# io.net
KiCad netlist of a schematic drawn in EAGLE
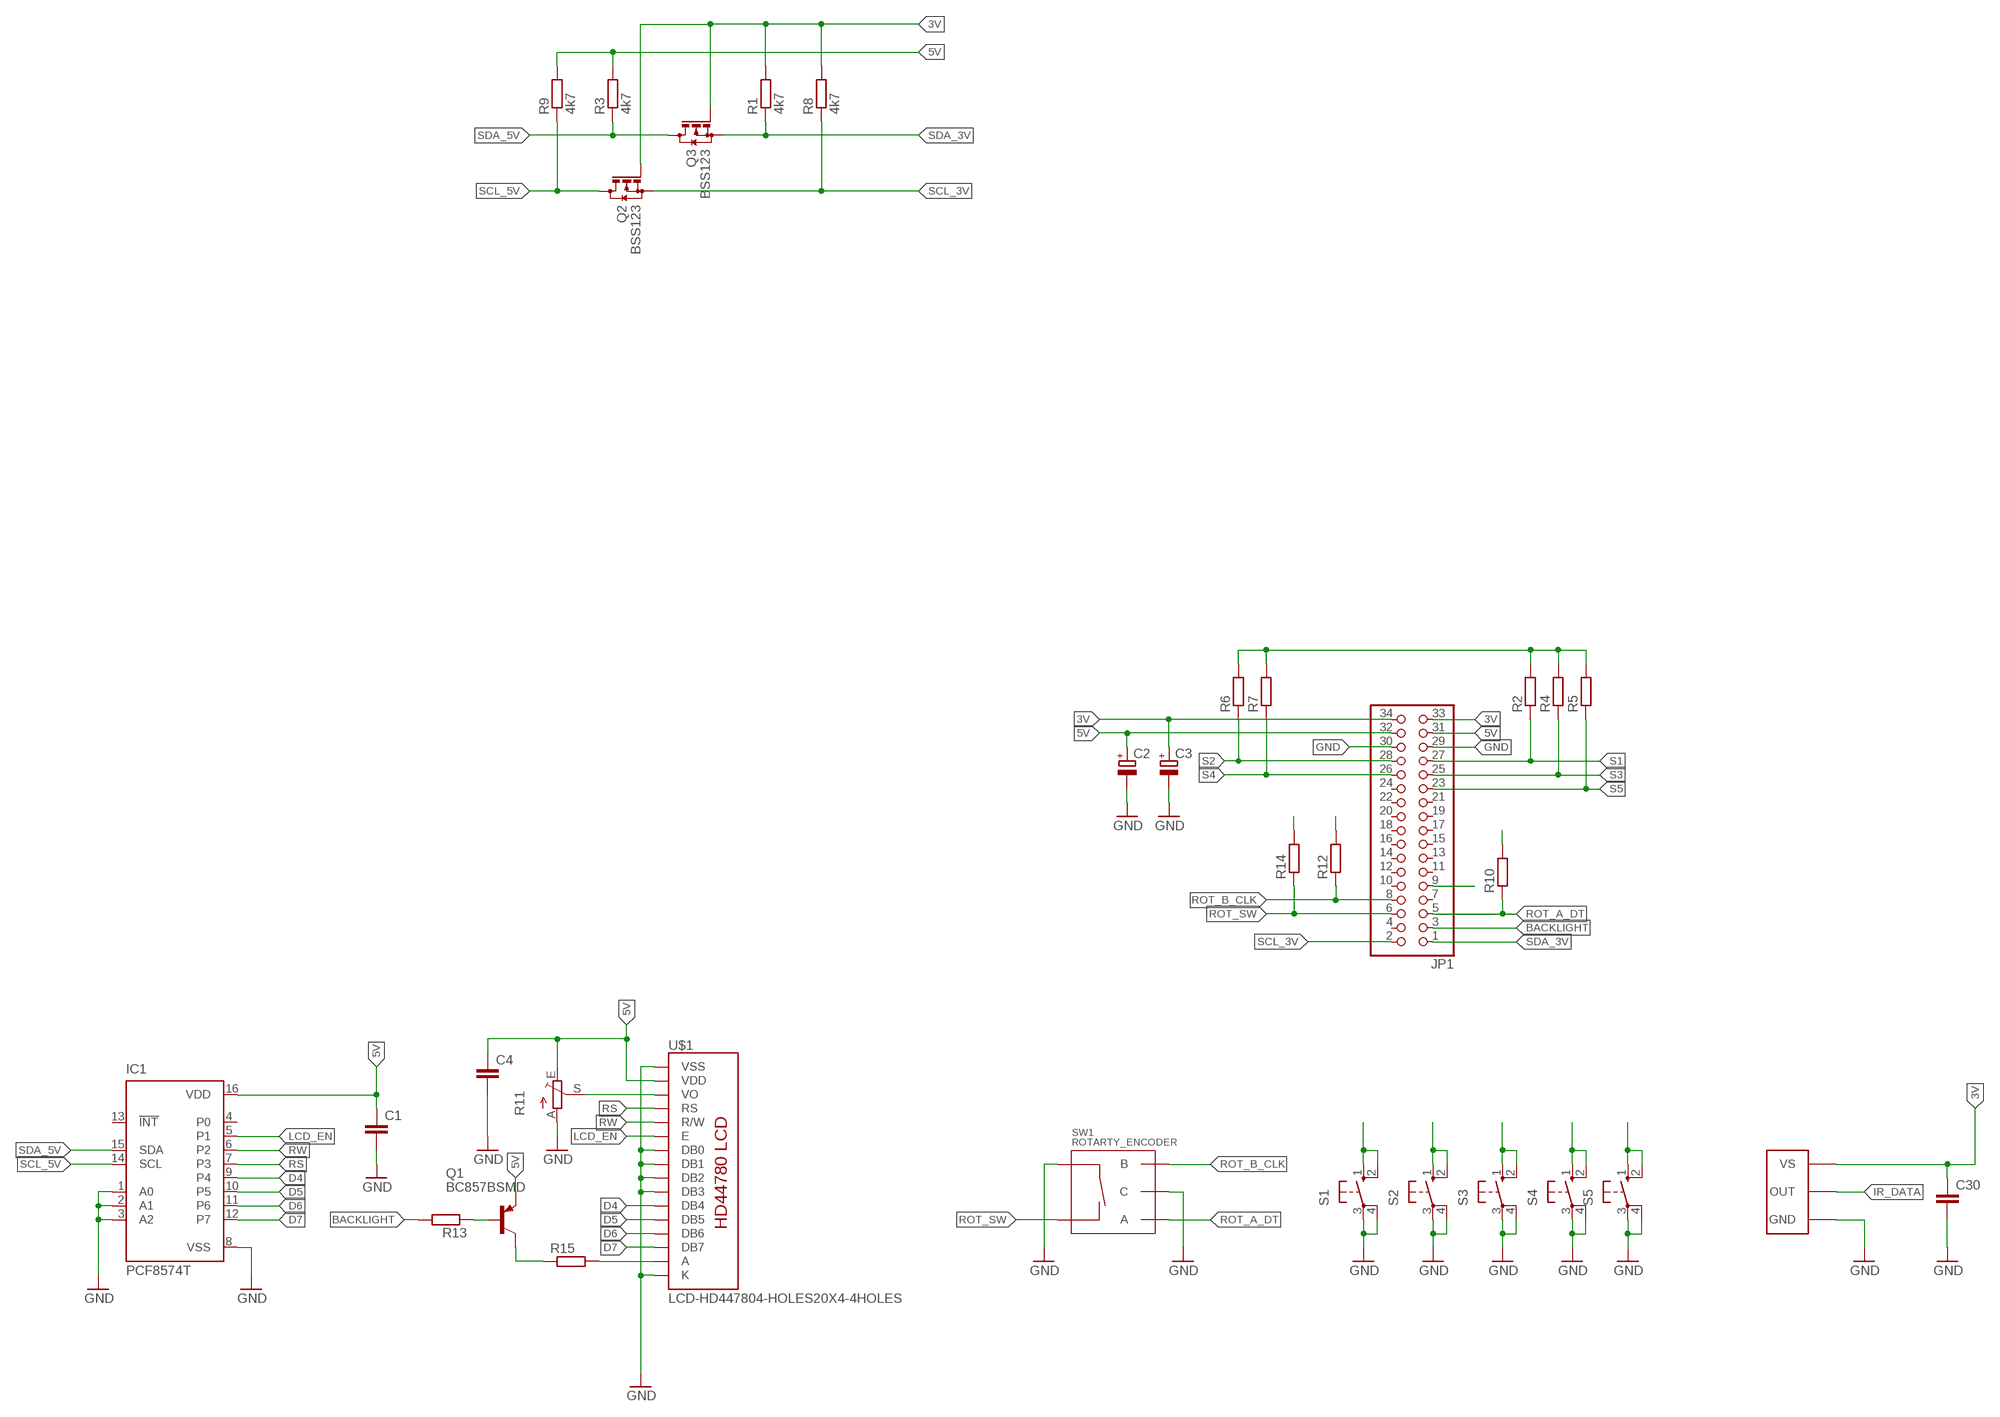
[diagram p0: schematic, sheet 1]

(export (version "E")
  (design (tool "Eeschema 10.0.6"))
  (components
    (comp (ref "C1")
      (value "C-EUC0603")
      (footprint "eagle-import:C0603")
      (libsource (lib "eagle-import") (part "C-EUC0603"))
    )
    (comp (ref "C2")
      (value "CPOL-EUSMCD")
      (footprint "eagle-import:SMC_D")
      (libsource (lib "eagle-import") (part "CPOL-EUSMCD"))
    )
    (comp (ref "C3")
      (value "CPOL-EUSMCB")
      (footprint "eagle-import:SMC_B")
      (libsource (lib "eagle-import") (part "CPOL-EUSMCB"))
    )
    (comp (ref "C4")
      (value "C-EUC1206")
      (footprint "eagle-import:C1206")
      (libsource (lib "eagle-import") (part "C-EUC1206"))
    )
    (comp (ref "C30")
      (value "C-EUC1206")
      (footprint "eagle-import:C1206")
      (libsource (lib "eagle-import") (part "C-EUC1206"))
    )
    (comp (ref "IC1")
      (value "PCF8574T")
      (footprint "eagle-import:SO16W")
      (fields (field (name "MPN") "PCF8574T/3,512"))
      (libsource (lib "eagle-import") (part "PCF8574T"))
    )
    (comp (ref "JP1")
      (value "PINHD-2X17_2.54-SMD")
      (footprint "eagle-import:2X17SMD")
      (libsource (lib "eagle-import") (part "PINHD-2X17_2.54-SMD"))
    )
    (comp (ref "Q1")
      (value "BC857BSMD")
      (footprint "eagle-import:SOT23-BEC")
      (libsource (lib "eagle-import") (part "BC857SMDB"))
    )
    (comp (ref "Q2")
      (value "BSS123")
      (footprint "eagle-import:SOT23")
      (libsource (lib "eagle-import") (part "BSS123"))
    )
    (comp (ref "Q3")
      (value "BSS123")
      (footprint "eagle-import:SOT23")
      (libsource (lib "eagle-import") (part "BSS123"))
    )
    (comp (ref "R1")
      (value "4k7")
      (footprint "eagle-import:R0603")
      (libsource (lib "eagle-import") (part "R-EU_R0603"))
    )
    (comp (ref "R2")
      (value "R-EU_0204/7")
      (footprint "eagle-import:0204_7")
      (libsource (lib "eagle-import") (part "R-EU_0204/7"))
    )
    (comp (ref "R3")
      (value "4k7")
      (footprint "eagle-import:R0603")
      (libsource (lib "eagle-import") (part "R-EU_R0603"))
    )
    (comp (ref "R4")
      (value "R-EU_0204/7")
      (footprint "eagle-import:0204_7")
      (libsource (lib "eagle-import") (part "R-EU_0204/7"))
    )
    (comp (ref "R5")
      (value "R-EU_0204/7")
      (footprint "eagle-import:0204_7")
      (libsource (lib "eagle-import") (part "R-EU_0204/7"))
    )
    (comp (ref "R6")
      (value "R-EU_0204/7")
      (footprint "eagle-import:0204_7")
      (libsource (lib "eagle-import") (part "R-EU_0204/7"))
    )
    (comp (ref "R7")
      (value "R-EU_0204/7")
      (footprint "eagle-import:0204_7")
      (libsource (lib "eagle-import") (part "R-EU_0204/7"))
    )
    (comp (ref "R8")
      (value "4k7")
      (footprint "eagle-import:R0603")
      (libsource (lib "eagle-import") (part "R-EU_R0603"))
    )
    (comp (ref "R9")
      (value "4k7")
      (footprint "eagle-import:R0603")
      (libsource (lib "eagle-import") (part "R-EU_R0603"))
    )
    (comp (ref "R10")
      (value "R-EU_0204/7")
      (footprint "eagle-import:0204_7")
      (libsource (lib "eagle-import") (part "R-EU_0204/7"))
    )
    (comp (ref "R11")
      (value "TRIM_EU-B25U")
      (footprint "eagle-import:B25U")
      (libsource (lib "eagle-import") (part "TRIM_EU-B25U"))
    )
    (comp (ref "R12")
      (value "R-EU_0204/7")
      (footprint "eagle-import:0204_7")
      (libsource (lib "eagle-import") (part "R-EU_0204/7"))
    )
    (comp (ref "R13")
      (value "R-EU_0204/7")
      (footprint "eagle-import:0204_7")
      (libsource (lib "eagle-import") (part "R-EU_0204/7"))
    )
    (comp (ref "R14")
      (value "R-EU_0204/7")
      (footprint "eagle-import:0204_7")
      (libsource (lib "eagle-import") (part "R-EU_0204/7"))
    )
    (comp (ref "R15")
      (value "R-EU_R0603")
      (footprint "eagle-import:R0603")
      (libsource (lib "eagle-import") (part "R-EU_R0603"))
    )
    (comp (ref "S1")
      (value "40-XX")
      (footprint "eagle-import:B3F-40XX")
      (fields (field (name "MF") "OMRON COMPONENTS USA") (field (name "MPN") "B3F-4000"))
      (libsource (lib "eagle-import") (part "40-XX"))
    )
    (comp (ref "S2")
      (value "40-XX")
      (footprint "eagle-import:B3F-40XX")
      (fields (field (name "MF") "OMRON COMPONENTS USA") (field (name "MPN") "B3F-4000"))
      (libsource (lib "eagle-import") (part "40-XX"))
    )
    (comp (ref "S3")
      (value "40-XX")
      (footprint "eagle-import:B3F-40XX")
      (fields (field (name "MF") "OMRON COMPONENTS USA") (field (name "MPN") "B3F-4000"))
      (libsource (lib "eagle-import") (part "40-XX"))
    )
    (comp (ref "S4")
      (value "40-XX")
      (footprint "eagle-import:B3F-40XX")
      (fields (field (name "MF") "OMRON COMPONENTS USA") (field (name "MPN") "B3F-4000"))
      (libsource (lib "eagle-import") (part "40-XX"))
    )
    (comp (ref "S5")
      (value "40-XX")
      (footprint "eagle-import:B3F-40XX")
      (fields (field (name "MF") "OMRON COMPONENTS USA") (field (name "MPN") "B3F-4000"))
      (libsource (lib "eagle-import") (part "40-XX"))
    )
    (comp (ref "SW1")
      (value "ROTARTY_ENCODER")
      (footprint "eagle-import:ROTARY_ENC_PLAIN")
      (libsource (lib "eagle-import") (part "ROTARTY_ENCODER"))
    )
    (comp (ref "U$1")
      (value "LCD-HD447804-HOLES20X4-4HOLES")
      (footprint "eagle-import:LCD-20X4-4HOLES")
      (libsource (lib "eagle-import") (part "LCD-HD4478020X4-4HOLES4-HOLES"))
    )
    (comp (ref "U$5")
      (value "TSOP312XVERTICAL")
      (footprint "eagle-import:TSOP312X_VERT")
      (libsource (lib "eagle-import") (part "TSOP312XVERTICAL"))
    )
  )
  (nets
    (net (code "1") (name "3V") (class "Default")
      (node (ref "C3") (pin "+") (pinfunction "+_+") (pintype "passive"))
      (node (ref "C30") (pin "1") (pinfunction "1_1") (pintype "passive"))
      (node (ref "JP1") (pin "33") (pinfunction "33_33") (pintype "passive"))
      (node (ref "JP1") (pin "34") (pinfunction "34_34") (pintype "passive"))
      (node (ref "Q2") (pin "1") (pinfunction "G_1") (pintype "passive"))
      (node (ref "Q3") (pin "1") (pinfunction "G_1") (pintype "passive"))
      (node (ref "R1") (pin "2") (pinfunction "2_2") (pintype "passive"))
      (node (ref "R10") (pin "2") (pinfunction "2_2") (pintype "passive"))
      (node (ref "R12") (pin "2") (pinfunction "2_2") (pintype "passive"))
      (node (ref "R14") (pin "2") (pinfunction "2_2") (pintype "passive"))
      (node (ref "R2") (pin "2") (pinfunction "2_2") (pintype "passive"))
      (node (ref "R4") (pin "2") (pinfunction "2_2") (pintype "passive"))
      (node (ref "R5") (pin "2") (pinfunction "2_2") (pintype "passive"))
      (node (ref "R6") (pin "2") (pinfunction "2_2") (pintype "passive"))
      (node (ref "R7") (pin "2") (pinfunction "2_2") (pintype "passive"))
      (node (ref "R8") (pin "2") (pinfunction "2_2") (pintype "passive"))
      (node (ref "U$5") (pin "2") (pinfunction "VS_2") (pintype "bidirectional"))
    )
    (net (code "2") (name "5V") (class "Default")
      (node (ref "C1") (pin "1") (pinfunction "1_1") (pintype "passive"))
      (node (ref "C2") (pin "+") (pinfunction "+_+") (pintype "passive"))
      (node (ref "C4") (pin "1") (pinfunction "1_1") (pintype "passive"))
      (node (ref "IC1") (pin "16") (pinfunction "VDD_16") (pintype "power_in"))
      (node (ref "JP1") (pin "31") (pinfunction "31_31") (pintype "passive"))
      (node (ref "JP1") (pin "32") (pinfunction "32_32") (pintype "passive"))
      (node (ref "Q1") (pin "E") (pinfunction "E_E") (pintype "passive"))
      (node (ref "R11") (pin "E") (pinfunction "E_E") (pintype "passive"))
      (node (ref "R3") (pin "2") (pinfunction "2_2") (pintype "passive"))
      (node (ref "R9") (pin "2") (pinfunction "2_2") (pintype "passive"))
      (node (ref "U$1") (pin "P$2") (pinfunction "VDD_P$2") (pintype "power_in"))
    )
    (net (code "3") (name "BACKLIGHT") (class "Default")
      (node (ref "JP1") (pin "3") (pinfunction "3_3") (pintype "passive"))
      (node (ref "R13") (pin "2") (pinfunction "2_2") (pintype "passive"))
    )
    (net (code "4") (name "D4") (class "Default")
      (node (ref "IC1") (pin "9") (pinfunction "P4_9") (pintype "bidirectional"))
      (node (ref "U$1") (pin "P$11") (pinfunction "DB4_P$11") (pintype "bidirectional"))
    )
    (net (code "5") (name "D5") (class "Default")
      (node (ref "IC1") (pin "10") (pinfunction "P5_10") (pintype "bidirectional"))
      (node (ref "U$1") (pin "P$12") (pinfunction "DB5_P$12") (pintype "bidirectional"))
    )
    (net (code "6") (name "D6") (class "Default")
      (node (ref "IC1") (pin "11") (pinfunction "P6_11") (pintype "bidirectional"))
      (node (ref "U$1") (pin "P$13") (pinfunction "DB6_P$13") (pintype "bidirectional"))
    )
    (net (code "7") (name "D7") (class "Default")
      (node (ref "IC1") (pin "12") (pinfunction "P7_12") (pintype "bidirectional"))
      (node (ref "U$1") (pin "P$14") (pinfunction "DB7_P$14") (pintype "bidirectional"))
    )
    (net (code "8") (name "GND") (class "Default")
      (node (ref "C1") (pin "2") (pinfunction "2_2") (pintype "passive"))
      (node (ref "C2") (pin "-") (pinfunction "-_-") (pintype "passive"))
      (node (ref "C3") (pin "-") (pinfunction "-_-") (pintype "passive"))
      (node (ref "C30") (pin "2") (pinfunction "2_2") (pintype "passive"))
      (node (ref "C4") (pin "2") (pinfunction "2_2") (pintype "passive"))
      (node (ref "IC1") (pin "1") (pinfunction "A0_1") (pintype "input"))
      (node (ref "IC1") (pin "2") (pinfunction "A1_2") (pintype "input"))
      (node (ref "IC1") (pin "3") (pinfunction "A2_3") (pintype "input"))
      (node (ref "IC1") (pin "8") (pinfunction "VSS_8") (pintype "power_in"))
      (node (ref "JP1") (pin "29") (pinfunction "29_29") (pintype "passive"))
      (node (ref "JP1") (pin "30") (pinfunction "30_30") (pintype "passive"))
      (node (ref "R11") (pin "A") (pinfunction "A_A") (pintype "passive"))
      (node (ref "S1") (pin "3") (pinfunction "P_3") (pintype "passive"))
      (node (ref "S1") (pin "4") (pinfunction "P1_4") (pintype "passive"))
      (node (ref "S2") (pin "3") (pinfunction "P_3") (pintype "passive"))
      (node (ref "S2") (pin "4") (pinfunction "P1_4") (pintype "passive"))
      (node (ref "S3") (pin "3") (pinfunction "P_3") (pintype "passive"))
      (node (ref "S3") (pin "4") (pinfunction "P1_4") (pintype "passive"))
      (node (ref "S4") (pin "3") (pinfunction "P_3") (pintype "passive"))
      (node (ref "S4") (pin "4") (pinfunction "P1_4") (pintype "passive"))
      (node (ref "S5") (pin "3") (pinfunction "P_3") (pintype "passive"))
      (node (ref "S5") (pin "4") (pinfunction "P1_4") (pintype "passive"))
      (node (ref "SW1") (pin "C") (pinfunction "C_C") (pintype "bidirectional"))
      (node (ref "SW1") (pin "SW+") (pinfunction "SW+_SW+") (pintype "bidirectional"))
      (node (ref "U$1") (pin "P$1") (pinfunction "VSS_P$1") (pintype "power_in"))
      (node (ref "U$1") (pin "P$10") (pinfunction "DB3_P$10") (pintype "bidirectional"))
      (node (ref "U$1") (pin "P$16") (pinfunction "K_P$16") (pintype "power_in"))
      (node (ref "U$1") (pin "P$7") (pinfunction "DB0_P$7") (pintype "bidirectional"))
      (node (ref "U$1") (pin "P$8") (pinfunction "DB1_P$8") (pintype "bidirectional"))
      (node (ref "U$1") (pin "P$9") (pinfunction "DB2_P$9") (pintype "bidirectional"))
      (node (ref "U$5") (pin "1") (pinfunction "GND_1") (pintype "bidirectional"))
    )
    (net (code "9") (name "IR_DATA") (class "Default")
      (node (ref "JP1") (pin "9") (pinfunction "9_9") (pintype "passive"))
      (node (ref "U$5") (pin "3") (pinfunction "OUT_3") (pintype "bidirectional"))
    )
    (net (code "10") (name "LCD_EN") (class "Default")
      (node (ref "IC1") (pin "5") (pinfunction "P1_5") (pintype "bidirectional"))
      (node (ref "U$1") (pin "P$6") (pinfunction "E_P$6") (pintype "input"))
    )
    (net (code "11") (name "Net-(Q1-PadB)") (class "Default")
      (node (ref "Q1") (pin "B") (pinfunction "B_B") (pintype "passive"))
      (node (ref "R13") (pin "1") (pinfunction "1_1") (pintype "passive"))
    )
    (net (code "12") (name "Net-(Q1-PadC)") (class "Default")
      (node (ref "Q1") (pin "C") (pinfunction "C_C") (pintype "passive"))
      (node (ref "R15") (pin "1") (pinfunction "1_1") (pintype "passive"))
    )
    (net (code "13") (name "Net-(U$1-A)") (class "Default")
      (node (ref "R15") (pin "2") (pinfunction "2_2") (pintype "passive"))
      (node (ref "U$1") (pin "P$15") (pinfunction "A_P$15") (pintype "power_in"))
    )
    (net (code "14") (name "Net-(U$1-VO)") (class "Default")
      (node (ref "R11") (pin "S") (pinfunction "S_S") (pintype "passive"))
      (node (ref "U$1") (pin "P$3") (pinfunction "VO_P$3") (pintype "bidirectional"))
    )
    (net (code "15") (name "ROT_A_DT") (class "Default")
      (node (ref "JP1") (pin "5") (pinfunction "5_5") (pintype "passive"))
      (node (ref "R10") (pin "1") (pinfunction "1_1") (pintype "passive"))
      (node (ref "SW1") (pin "A") (pinfunction "A_A") (pintype "bidirectional"))
    )
    (net (code "16") (name "ROT_B_CLK") (class "Default")
      (node (ref "JP1") (pin "8") (pinfunction "8_8") (pintype "passive"))
      (node (ref "R12") (pin "1") (pinfunction "1_1") (pintype "passive"))
      (node (ref "SW1") (pin "B") (pinfunction "B_B") (pintype "bidirectional"))
    )
    (net (code "17") (name "ROT_SW") (class "Default")
      (node (ref "JP1") (pin "6") (pinfunction "6_6") (pintype "passive"))
      (node (ref "R14") (pin "1") (pinfunction "1_1") (pintype "passive"))
      (node (ref "SW1") (pin "SW-") (pinfunction "SW-_SW-") (pintype "bidirectional"))
    )
    (net (code "18") (name "RS") (class "Default")
      (node (ref "IC1") (pin "7") (pinfunction "P3_7") (pintype "bidirectional"))
      (node (ref "U$1") (pin "P$4") (pinfunction "RS_P$4") (pintype "input"))
    )
    (net (code "19") (name "RW") (class "Default")
      (node (ref "IC1") (pin "6") (pinfunction "P2_6") (pintype "bidirectional"))
      (node (ref "U$1") (pin "P$5") (pinfunction "R/W_P$5") (pintype "input"))
    )
    (net (code "20") (name "S1") (class "Default")
      (node (ref "JP1") (pin "27") (pinfunction "27_27") (pintype "passive"))
      (node (ref "R2") (pin "1") (pinfunction "1_1") (pintype "passive"))
      (node (ref "S1") (pin "1") (pinfunction "S_1") (pintype "passive"))
      (node (ref "S1") (pin "2") (pinfunction "S1_2") (pintype "passive"))
    )
    (net (code "21") (name "S2") (class "Default")
      (node (ref "JP1") (pin "28") (pinfunction "28_28") (pintype "passive"))
      (node (ref "R6") (pin "1") (pinfunction "1_1") (pintype "passive"))
      (node (ref "S2") (pin "1") (pinfunction "S_1") (pintype "passive"))
      (node (ref "S2") (pin "2") (pinfunction "S1_2") (pintype "passive"))
    )
    (net (code "22") (name "S3") (class "Default")
      (node (ref "JP1") (pin "25") (pinfunction "25_25") (pintype "passive"))
      (node (ref "R4") (pin "1") (pinfunction "1_1") (pintype "passive"))
      (node (ref "S3") (pin "1") (pinfunction "S_1") (pintype "passive"))
      (node (ref "S3") (pin "2") (pinfunction "S1_2") (pintype "passive"))
    )
    (net (code "23") (name "S4") (class "Default")
      (node (ref "JP1") (pin "26") (pinfunction "26_26") (pintype "passive"))
      (node (ref "R7") (pin "1") (pinfunction "1_1") (pintype "passive"))
      (node (ref "S4") (pin "1") (pinfunction "S_1") (pintype "passive"))
      (node (ref "S4") (pin "2") (pinfunction "S1_2") (pintype "passive"))
    )
    (net (code "24") (name "S5") (class "Default")
      (node (ref "JP1") (pin "23") (pinfunction "23_23") (pintype "passive"))
      (node (ref "R5") (pin "1") (pinfunction "1_1") (pintype "passive"))
      (node (ref "S5") (pin "1") (pinfunction "S_1") (pintype "passive"))
      (node (ref "S5") (pin "2") (pinfunction "S1_2") (pintype "passive"))
    )
    (net (code "25") (name "SCL_3V") (class "Default")
      (node (ref "JP1") (pin "2") (pinfunction "2_2") (pintype "passive"))
      (node (ref "Q2") (pin "2") (pinfunction "S_2") (pintype "passive"))
      (node (ref "R8") (pin "1") (pinfunction "1_1") (pintype "passive"))
    )
    (net (code "26") (name "SCL_5V") (class "Default")
      (node (ref "IC1") (pin "14") (pinfunction "SCL_14") (pintype "input"))
      (node (ref "Q2") (pin "3") (pinfunction "D_3") (pintype "passive"))
      (node (ref "R9") (pin "1") (pinfunction "1_1") (pintype "passive"))
    )
    (net (code "27") (name "SDA_3V") (class "Default")
      (node (ref "JP1") (pin "1") (pinfunction "1_1") (pintype "passive"))
      (node (ref "Q3") (pin "2") (pinfunction "S_2") (pintype "passive"))
      (node (ref "R1") (pin "1") (pinfunction "1_1") (pintype "passive"))
    )
    (net (code "28") (name "SDA_5V") (class "Default")
      (node (ref "IC1") (pin "15") (pinfunction "SDA_15") (pintype "bidirectional"))
      (node (ref "Q3") (pin "3") (pinfunction "D_3") (pintype "passive"))
      (node (ref "R3") (pin "1") (pinfunction "1_1") (pintype "passive"))
    )
    (net (code "29") (name "unconnected-(IC1-P0-Pad4)") (class "Default")
      (node (ref "IC1") (pin "4") (pinfunction "P0_4") (pintype "bidirectional"))
    )
    (net (code "30") (name "unconnected-(IC1-~{INT}-Pad13)") (class "Default")
      (node (ref "IC1") (pin "13") (pinfunction "~{INT}_13") (pintype "output"))
    )
    (net (code "31") (name "unconnected-(JP1-Pad4)") (class "Default")
      (node (ref "JP1") (pin "4") (pinfunction "4_4") (pintype "passive"))
    )
    (net (code "32") (name "unconnected-(JP1-Pad7)") (class "Default")
      (node (ref "JP1") (pin "7") (pinfunction "7_7") (pintype "passive"))
    )
    (net (code "33") (name "unconnected-(JP1-Pad10)") (class "Default")
      (node (ref "JP1") (pin "10") (pinfunction "10_10") (pintype "passive"))
    )
    (net (code "34") (name "unconnected-(JP1-Pad11)") (class "Default")
      (node (ref "JP1") (pin "11") (pinfunction "11_11") (pintype "passive"))
    )
    (net (code "35") (name "unconnected-(JP1-Pad12)") (class "Default")
      (node (ref "JP1") (pin "12") (pinfunction "12_12") (pintype "passive"))
    )
    (net (code "36") (name "unconnected-(JP1-Pad13)") (class "Default")
      (node (ref "JP1") (pin "13") (pinfunction "13_13") (pintype "passive"))
    )
    (net (code "37") (name "unconnected-(JP1-Pad14)") (class "Default")
      (node (ref "JP1") (pin "14") (pinfunction "14_14") (pintype "passive"))
    )
    (net (code "38") (name "unconnected-(JP1-Pad15)") (class "Default")
      (node (ref "JP1") (pin "15") (pinfunction "15_15") (pintype "passive"))
    )
    (net (code "39") (name "unconnected-(JP1-Pad16)") (class "Default")
      (node (ref "JP1") (pin "16") (pinfunction "16_16") (pintype "passive"))
    )
    (net (code "40") (name "unconnected-(JP1-Pad17)") (class "Default")
      (node (ref "JP1") (pin "17") (pinfunction "17_17") (pintype "passive"))
    )
    (net (code "41") (name "unconnected-(JP1-Pad18)") (class "Default")
      (node (ref "JP1") (pin "18") (pinfunction "18_18") (pintype "passive"))
    )
    (net (code "42") (name "unconnected-(JP1-Pad19)") (class "Default")
      (node (ref "JP1") (pin "19") (pinfunction "19_19") (pintype "passive"))
    )
    (net (code "43") (name "unconnected-(JP1-Pad20)") (class "Default")
      (node (ref "JP1") (pin "20") (pinfunction "20_20") (pintype "passive"))
    )
    (net (code "44") (name "unconnected-(JP1-Pad21)") (class "Default")
      (node (ref "JP1") (pin "21") (pinfunction "21_21") (pintype "passive"))
    )
    (net (code "45") (name "unconnected-(JP1-Pad22)") (class "Default")
      (node (ref "JP1") (pin "22") (pinfunction "22_22") (pintype "passive"))
    )
    (net (code "46") (name "unconnected-(JP1-Pad24)") (class "Default")
      (node (ref "JP1") (pin "24") (pinfunction "24_24") (pintype "passive"))
    )
  )
)
